# DE1_SIDE_SDRAM.net
KiCad netlist of a schematic drawn in Altium Designer
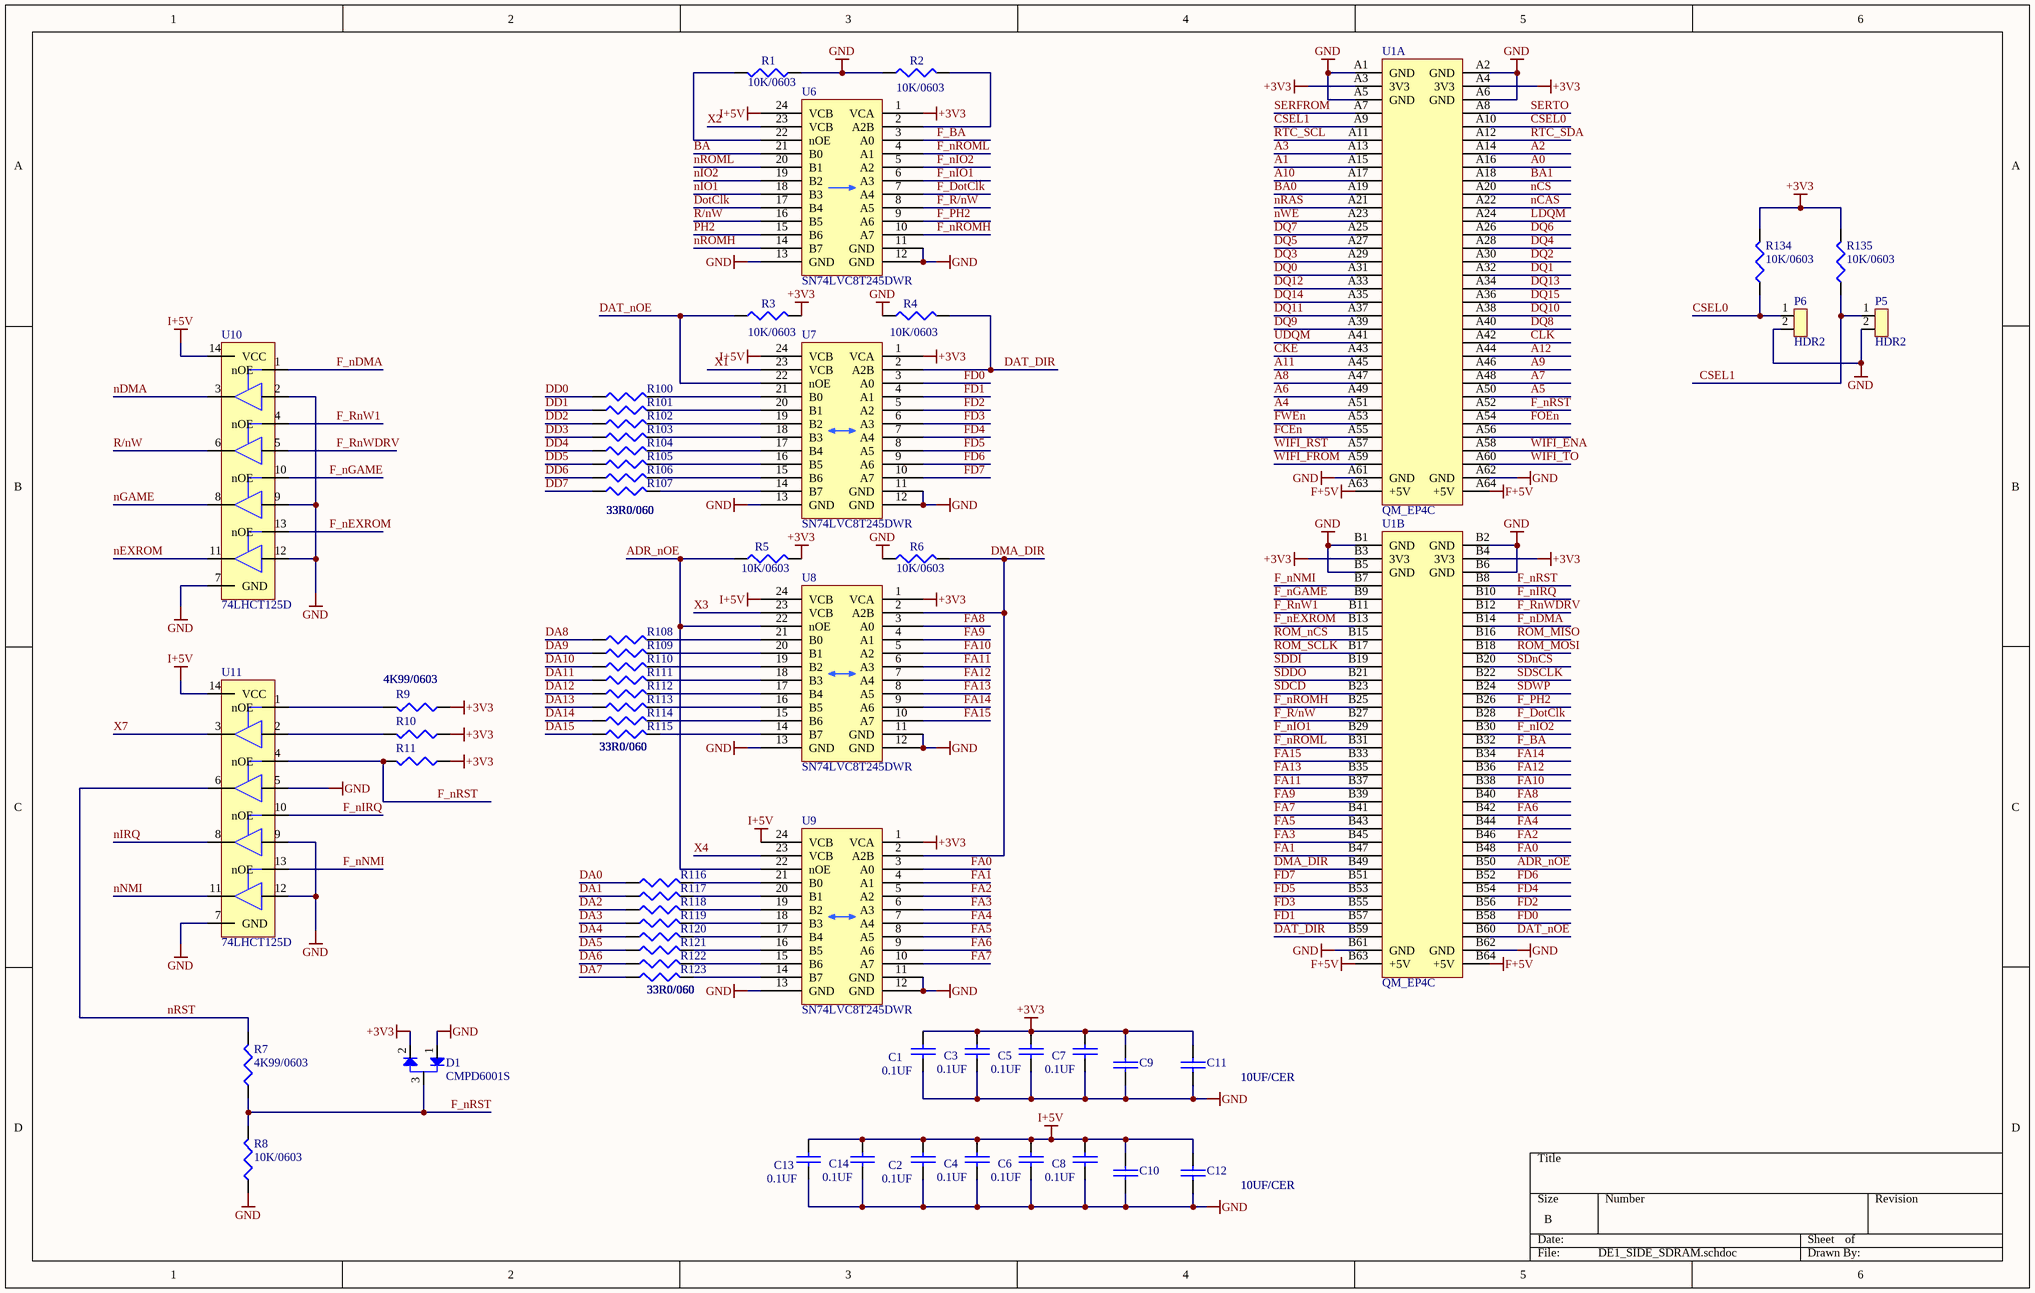
[diagram p0: DE1_SIDE_SDRAM.schdoc]

(export (version "E")
  (design (tool "Eeschema 10.0.6"))
  (components
    (comp (ref "C1")
      (value "0.1UF")
      (footprint "0603")
      (description "CAP .10UF 16V CERAMIC X7R 0603")
      (libsource (lib "*") (part "0.1UF"))
    )
    (comp (ref "C2")
      (value "0.1UF")
      (footprint "0603")
      (description "CAP .10UF 16V CERAMIC X7R 0603")
      (libsource (lib "*") (part "0.1UF"))
    )
    (comp (ref "C3")
      (value "0.1UF")
      (footprint "0603")
      (description "CAP .10UF 16V CERAMIC X7R 0603")
      (libsource (lib "*") (part "0.1UF"))
    )
    (comp (ref "C4")
      (value "0.1UF")
      (footprint "0603")
      (description "CAP .10UF 16V CERAMIC X7R 0603")
      (libsource (lib "*") (part "0.1UF"))
    )
    (comp (ref "C5")
      (value "0.1UF")
      (footprint "0603")
      (description "CAP .10UF 16V CERAMIC X7R 0603")
      (libsource (lib "*") (part "0.1UF"))
    )
    (comp (ref "C6")
      (value "0.1UF")
      (footprint "0603")
      (description "CAP .10UF 16V CERAMIC X7R 0603")
      (libsource (lib "*") (part "0.1UF"))
    )
    (comp (ref "C7")
      (value "0.1UF")
      (footprint "0603")
      (description "CAP .10UF 16V CERAMIC X7R 0603")
      (libsource (lib "*") (part "0.1UF"))
    )
    (comp (ref "C8")
      (value "0.1UF")
      (footprint "0603")
      (description "CAP .10UF 16V CERAMIC X7R 0603")
      (libsource (lib "*") (part "0.1UF"))
    )
    (comp (ref "C9")
      (value "10UF/CER")
      (footprint "0805")
      (description "10µF ±10% 25V Ceramic Capacitor X7S 0805")
      (libsource (lib "*") (part "10UF/CER"))
    )
    (comp (ref "C10")
      (value "10UF/CER")
      (footprint "0805")
      (description "10µF ±10% 25V Ceramic Capacitor X7S 0805")
      (libsource (lib "*") (part "10UF/CER"))
    )
    (comp (ref "C11")
      (value "10UF/CER")
      (footprint "0805")
      (description "10µF ±10% 25V Ceramic Capacitor X7S 0805")
      (libsource (lib "*") (part "10UF/CER"))
    )
    (comp (ref "C12")
      (value "10UF/CER")
      (footprint "0805")
      (description "10µF ±10% 25V Ceramic Capacitor X7S 0805")
      (libsource (lib "*") (part "10UF/CER"))
    )
    (comp (ref "C13")
      (value "0.1UF")
      (footprint "0603")
      (description "CAP .10UF 16V CERAMIC X7R 0603")
      (libsource (lib "*") (part "0.1UF"))
    )
    (comp (ref "C14")
      (value "0.1UF")
      (footprint "0603")
      (description "CAP .10UF 16V CERAMIC X7R 0603")
      (libsource (lib "*") (part "0.1UF"))
    )
    (comp (ref "D1")
      (value "CMPD6001S")
      (footprint "SOT-23")
      (description "Diode Array 1 Pair Series Connection Standard 75V 250mA Surface Mount TO-236-3, SC-59, SOT-23-3")
      (fields (field (name "MFG") "Central Semiconductor"))
      (libsource (lib "C64Interface") (part "CMPD6001S"))
    )
    (comp (ref "P5") (value "HDR2") (footprint "HDR2") (libsource (lib "C64Interface") (part "HDR2")))
    (comp (ref "P6") (value "HDR2") (footprint "HDR2") (libsource (lib "C64Interface") (part "HDR2")))
    (comp (ref "R1")
      (value "10K/0603")
      (footprint "0603")
      (description "RES 10.0K OHM 1/10W 1% 0603 SMD")
      (libsource (lib "*") (part "10K/0603"))
    )
    (comp (ref "R2")
      (value "10K/0603")
      (footprint "0603")
      (description "RES 10.0K OHM 1/10W 1% 0603 SMD")
      (libsource (lib "*") (part "10K/0603"))
    )
    (comp (ref "R3")
      (value "10K/0603")
      (footprint "0603")
      (description "RES 10.0K OHM 1/10W 1% 0603 SMD")
      (libsource (lib "*") (part "10K/0603"))
    )
    (comp (ref "R4")
      (value "10K/0603")
      (footprint "0603")
      (description "RES 10.0K OHM 1/10W 1% 0603 SMD")
      (libsource (lib "*") (part "10K/0603"))
    )
    (comp (ref "R5")
      (value "10K/0603")
      (footprint "0603")
      (description "RES 10.0K OHM 1/10W 1% 0603 SMD")
      (libsource (lib "*") (part "10K/0603"))
    )
    (comp (ref "R6")
      (value "10K/0603")
      (footprint "0603")
      (description "RES 10.0K OHM 1/10W 1% 0603 SMD")
      (libsource (lib "*") (part "10K/0603"))
    )
    (comp (ref "R7")
      (value "4K99/0603")
      (footprint "0603")
      (description "RES 4.99K OHM 1/10W 1% 0603 SMD")
      (fields (field (name "MFG") "Dale/Vishay"))
      (libsource (lib "C64Interface") (part "4K99/0603"))
    )
    (comp (ref "R8")
      (value "10K/0603")
      (footprint "0603")
      (description "RES 10.0K OHM 1/10W 1% 0603 SMD")
      (fields (field (name "MFG") "Dale/Vishay"))
      (libsource (lib "C64Interface") (part "10K/0603"))
    )
    (comp (ref "R9")
      (value "4K99/0603")
      (footprint "0603")
      (description "RES 4.99K OHM 1/10W 1% 0603 SMD")
      (fields (field (name "MFG") "Dale/Vishay"))
      (libsource (lib "C64Interface") (part "4K99/0603"))
    )
    (comp (ref "R10")
      (value "4K99/0603")
      (footprint "0603")
      (description "RES 4.99K OHM 1/10W 1% 0603 SMD")
      (fields (field (name "MFG") "Dale/Vishay"))
      (libsource (lib "C64Interface") (part "4K99/0603"))
    )
    (comp (ref "R11")
      (value "4K99/0603")
      (footprint "0603")
      (description "RES 4.99K OHM 1/10W 1% 0603 SMD")
      (fields (field (name "MFG") "Dale/Vishay"))
      (libsource (lib "C64Interface") (part "4K99/0603"))
    )
    (comp (ref "R100")
      (value "33R0/060")
      (footprint "0603")
      (description "33 Ohms ±1% 0.1W, 1/10W Chip Resistor 0603 (1608 Metric) Moisture Resistant Thick Film")
      (fields (field (name "MFG") "Yaego"))
      (libsource (lib "C64Interface") (part "33R0/060"))
    )
    (comp (ref "R101")
      (value "33R0/060")
      (footprint "0603")
      (description "33 Ohms ±1% 0.1W, 1/10W Chip Resistor 0603 (1608 Metric) Moisture Resistant Thick Film")
      (fields (field (name "MFG") "Yaego"))
      (libsource (lib "C64Interface") (part "33R0/060"))
    )
    (comp (ref "R102")
      (value "33R0/060")
      (footprint "0603")
      (description "33 Ohms ±1% 0.1W, 1/10W Chip Resistor 0603 (1608 Metric) Moisture Resistant Thick Film")
      (fields (field (name "MFG") "Yaego"))
      (libsource (lib "C64Interface") (part "33R0/060"))
    )
    (comp (ref "R103")
      (value "33R0/060")
      (footprint "0603")
      (description "33 Ohms ±1% 0.1W, 1/10W Chip Resistor 0603 (1608 Metric) Moisture Resistant Thick Film")
      (fields (field (name "MFG") "Yaego"))
      (libsource (lib "C64Interface") (part "33R0/060"))
    )
    (comp (ref "R104")
      (value "33R0/060")
      (footprint "0603")
      (description "33 Ohms ±1% 0.1W, 1/10W Chip Resistor 0603 (1608 Metric) Moisture Resistant Thick Film")
      (fields (field (name "MFG") "Yaego"))
      (libsource (lib "C64Interface") (part "33R0/060"))
    )
    (comp (ref "R105")
      (value "33R0/060")
      (footprint "0603")
      (description "33 Ohms ±1% 0.1W, 1/10W Chip Resistor 0603 (1608 Metric) Moisture Resistant Thick Film")
      (fields (field (name "MFG") "Yaego"))
      (libsource (lib "C64Interface") (part "33R0/060"))
    )
    (comp (ref "R106")
      (value "33R0/060")
      (footprint "0603")
      (description "33 Ohms ±1% 0.1W, 1/10W Chip Resistor 0603 (1608 Metric) Moisture Resistant Thick Film")
      (fields (field (name "MFG") "Yaego"))
      (libsource (lib "C64Interface") (part "33R0/060"))
    )
    (comp (ref "R107")
      (value "33R0/060")
      (footprint "0603")
      (description "33 Ohms ±1% 0.1W, 1/10W Chip Resistor 0603 (1608 Metric) Moisture Resistant Thick Film")
      (fields (field (name "MFG") "Yaego"))
      (libsource (lib "C64Interface") (part "33R0/060"))
    )
    (comp (ref "R108")
      (value "33R0/060")
      (footprint "0603")
      (description "33 Ohms ±1% 0.1W, 1/10W Chip Resistor 0603 (1608 Metric) Moisture Resistant Thick Film")
      (fields (field (name "MFG") "Yaego"))
      (libsource (lib "C64Interface") (part "33R0/060"))
    )
    (comp (ref "R109")
      (value "33R0/060")
      (footprint "0603")
      (description "33 Ohms ±1% 0.1W, 1/10W Chip Resistor 0603 (1608 Metric) Moisture Resistant Thick Film")
      (fields (field (name "MFG") "Yaego"))
      (libsource (lib "C64Interface") (part "33R0/060"))
    )
    (comp (ref "R110")
      (value "33R0/060")
      (footprint "0603")
      (description "33 Ohms ±1% 0.1W, 1/10W Chip Resistor 0603 (1608 Metric) Moisture Resistant Thick Film")
      (fields (field (name "MFG") "Yaego"))
      (libsource (lib "C64Interface") (part "33R0/060"))
    )
    (comp (ref "R111")
      (value "33R0/060")
      (footprint "0603")
      (description "33 Ohms ±1% 0.1W, 1/10W Chip Resistor 0603 (1608 Metric) Moisture Resistant Thick Film")
      (fields (field (name "MFG") "Yaego"))
      (libsource (lib "C64Interface") (part "33R0/060"))
    )
    (comp (ref "R112")
      (value "33R0/060")
      (footprint "0603")
      (description "33 Ohms ±1% 0.1W, 1/10W Chip Resistor 0603 (1608 Metric) Moisture Resistant Thick Film")
      (fields (field (name "MFG") "Yaego"))
      (libsource (lib "C64Interface") (part "33R0/060"))
    )
    (comp (ref "R113")
      (value "33R0/060")
      (footprint "0603")
      (description "33 Ohms ±1% 0.1W, 1/10W Chip Resistor 0603 (1608 Metric) Moisture Resistant Thick Film")
      (fields (field (name "MFG") "Yaego"))
      (libsource (lib "C64Interface") (part "33R0/060"))
    )
    (comp (ref "R114")
      (value "33R0/060")
      (footprint "0603")
      (description "33 Ohms ±1% 0.1W, 1/10W Chip Resistor 0603 (1608 Metric) Moisture Resistant Thick Film")
      (fields (field (name "MFG") "Yaego"))
      (libsource (lib "C64Interface") (part "33R0/060"))
    )
    (comp (ref "R115")
      (value "33R0/060")
      (footprint "0603")
      (description "33 Ohms ±1% 0.1W, 1/10W Chip Resistor 0603 (1608 Metric) Moisture Resistant Thick Film")
      (fields (field (name "MFG") "Yaego"))
      (libsource (lib "C64Interface") (part "33R0/060"))
    )
    (comp (ref "R116")
      (value "33R0/060")
      (footprint "0603")
      (description "33 Ohms ±1% 0.1W, 1/10W Chip Resistor 0603 (1608 Metric) Moisture Resistant Thick Film")
      (fields (field (name "MFG") "Yaego"))
      (libsource (lib "C64Interface") (part "33R0/060"))
    )
    (comp (ref "R117")
      (value "33R0/060")
      (footprint "0603")
      (description "33 Ohms ±1% 0.1W, 1/10W Chip Resistor 0603 (1608 Metric) Moisture Resistant Thick Film")
      (fields (field (name "MFG") "Yaego"))
      (libsource (lib "C64Interface") (part "33R0/060"))
    )
    (comp (ref "R118")
      (value "33R0/060")
      (footprint "0603")
      (description "33 Ohms ±1% 0.1W, 1/10W Chip Resistor 0603 (1608 Metric) Moisture Resistant Thick Film")
      (fields (field (name "MFG") "Yaego"))
      (libsource (lib "C64Interface") (part "33R0/060"))
    )
    (comp (ref "R119")
      (value "33R0/060")
      (footprint "0603")
      (description "33 Ohms ±1% 0.1W, 1/10W Chip Resistor 0603 (1608 Metric) Moisture Resistant Thick Film")
      (fields (field (name "MFG") "Yaego"))
      (libsource (lib "C64Interface") (part "33R0/060"))
    )
    (comp (ref "R120")
      (value "33R0/060")
      (footprint "0603")
      (description "33 Ohms ±1% 0.1W, 1/10W Chip Resistor 0603 (1608 Metric) Moisture Resistant Thick Film")
      (fields (field (name "MFG") "Yaego"))
      (libsource (lib "C64Interface") (part "33R0/060"))
    )
    (comp (ref "R121")
      (value "33R0/060")
      (footprint "0603")
      (description "33 Ohms ±1% 0.1W, 1/10W Chip Resistor 0603 (1608 Metric) Moisture Resistant Thick Film")
      (fields (field (name "MFG") "Yaego"))
      (libsource (lib "C64Interface") (part "33R0/060"))
    )
    (comp (ref "R122")
      (value "33R0/060")
      (footprint "0603")
      (description "33 Ohms ±1% 0.1W, 1/10W Chip Resistor 0603 (1608 Metric) Moisture Resistant Thick Film")
      (fields (field (name "MFG") "Yaego"))
      (libsource (lib "C64Interface") (part "33R0/060"))
    )
    (comp (ref "R123")
      (value "33R0/060")
      (footprint "0603")
      (description "33 Ohms ±1% 0.1W, 1/10W Chip Resistor 0603 (1608 Metric) Moisture Resistant Thick Film")
      (fields (field (name "MFG") "Yaego"))
      (libsource (lib "C64Interface") (part "33R0/060"))
    )
    (comp (ref "R134")
      (value "10K/0603")
      (footprint "0603")
      (description "RES 10.0K OHM 1/10W 1% 0603 SMD")
      (fields (field (name "MFG") "Dale/Vishay"))
      (libsource (lib "C64Interface") (part "10K/0603"))
    )
    (comp (ref "R135")
      (value "10K/0603")
      (footprint "0603")
      (description "RES 10.0K OHM 1/10W 1% 0603 SMD")
      (fields (field (name "MFG") "Dale/Vishay"))
      (libsource (lib "C64Interface") (part "10K/0603"))
    )
    (comp (ref "U1")
      (value "QM_EP4C")
      (footprint "QMTECH_EP4CE15")
      (libsource (lib "C64Interface") (part "QM_EP4C"))
    )
    (comp (ref "U6")
      (value "SN74LVC8T245DWR")
      (footprint "SOL-24")
      (description "Voltage Level Translator Bidirectional 1 Circuit 8 Channel 24-SOIC")
      (fields (field (name "MFG") "TI"))
      (libsource (lib "C64Interface") (part "SN74LVC8T245DWR"))
    )
    (comp (ref "U7")
      (value "SN74LVC8T245DWR")
      (footprint "SOL-24")
      (description "Voltage Level Translator Bidirectional 1 Circuit 8 Channel 24-SOIC")
      (fields (field (name "MFG") "TI"))
      (libsource (lib "C64Interface") (part "SN74LVC8T245DWR"))
    )
    (comp (ref "U8")
      (value "SN74LVC8T245DWR")
      (footprint "SOL-24")
      (description "Voltage Level Translator Bidirectional 1 Circuit 8 Channel 24-SOIC")
      (fields (field (name "MFG") "TI"))
      (libsource (lib "C64Interface") (part "SN74LVC8T245DWR"))
    )
    (comp (ref "U9")
      (value "SN74LVC8T245DWR")
      (footprint "SOL-24")
      (description "Voltage Level Translator Bidirectional 1 Circuit 8 Channel 24-SOIC")
      (fields (field (name "MFG") "TI"))
      (libsource (lib "C64Interface") (part "SN74LVC8T245DWR"))
    )
    (comp (ref "U10")
      (value "74LHCT125D")
      (footprint "SOP14")
      (description "Buffer, Non-Inverting 4 Element 1 Bit per Element 3-State Output 14-SOIC")
      (fields (field (name "MFG") "Nexpiria"))
      (libsource (lib "C64Interface") (part "74LHCT125D"))
    )
    (comp (ref "U11")
      (value "74LHCT125D")
      (footprint "SOP14")
      (description "Buffer, Non-Inverting 4 Element 1 Bit per Element 3-State Output 14-SOIC")
      (fields (field (name "MFG") "Nexpiria"))
      (libsource (lib "C64Interface") (part "74LHCT125D"))
    )
  )
  (nets
    (net (code "1") (name "+3V3") (class "Default")
      (node (ref "C1") (pin "1") (pintype "passive"))
      (node (ref "C11") (pin "2") (pintype "passive"))
      (node (ref "C3") (pin "1") (pintype "passive"))
      (node (ref "C5") (pin "1") (pintype "passive"))
      (node (ref "C7") (pin "1") (pintype "passive"))
      (node (ref "C9") (pin "2") (pintype "passive"))
      (node (ref "D1") (pin "2") (pintype "passive"))
      (node (ref "R10") (pin "1") (pintype "passive"))
      (node (ref "R11") (pin "1") (pintype "passive"))
      (node (ref "R134") (pin "2") (pintype "passive"))
      (node (ref "R135") (pin "2") (pintype "passive"))
      (node (ref "R3") (pin "2") (pintype "passive"))
      (node (ref "R5") (pin "2") (pintype "passive"))
      (node (ref "R9") (pin "1") (pintype "passive"))
      (node (ref "U1") (pin "A3") (pinfunction "3V3_A3") (pintype "passive"))
      (node (ref "U1") (pin "A4") (pinfunction "3V3_A4") (pintype "passive"))
      (node (ref "U1") (pin "B3") (pinfunction "3V3_B3") (pintype "passive"))
      (node (ref "U1") (pin "B4") (pinfunction "3V3_B4") (pintype "passive"))
      (node (ref "U6") (pin "1") (pinfunction "VCA_1") (pintype "passive"))
      (node (ref "U7") (pin "1") (pinfunction "VCA_1") (pintype "passive"))
      (node (ref "U8") (pin "1") (pinfunction "VCA_1") (pintype "passive"))
      (node (ref "U9") (pin "1") (pinfunction "VCA_1") (pintype "passive"))
    )
    (net (code "2") (name "/A0") (class "Default") (node (ref "U1") (pin "A16") (pintype "passive")))
    (net (code "3") (name "/A1") (class "Default") (node (ref "U1") (pin "A15") (pintype "passive")))
    (net (code "4") (name "/A2") (class "Default") (node (ref "U1") (pin "A14") (pintype "passive")))
    (net (code "5") (name "/A3") (class "Default") (node (ref "U1") (pin "A13") (pintype "passive")))
    (net (code "6") (name "/A4") (class "Default") (node (ref "U1") (pin "A51") (pintype "passive")))
    (net (code "7") (name "/A5") (class "Default") (node (ref "U1") (pin "A50") (pintype "passive")))
    (net (code "8") (name "/A6") (class "Default") (node (ref "U1") (pin "A49") (pintype "passive")))
    (net (code "9") (name "/A7") (class "Default") (node (ref "U1") (pin "A48") (pintype "passive")))
    (net (code "10") (name "/A8") (class "Default") (node (ref "U1") (pin "A47") (pintype "passive")))
    (net (code "11") (name "/A9") (class "Default") (node (ref "U1") (pin "A46") (pintype "passive")))
    (net (code "12") (name "/A10") (class "Default") (node (ref "U1") (pin "A17") (pintype "passive")))
    (net (code "13") (name "/A11") (class "Default") (node (ref "U1") (pin "A45") (pintype "passive")))
    (net (code "14") (name "/A12") (class "Default") (node (ref "U1") (pin "A44") (pintype "passive")))
    (net (code "15") (name "/ADR_nOE") (class "Default")
      (node (ref "R5") (pin "1") (pintype "passive"))
      (node (ref "U1") (pin "B50") (pintype "passive"))
      (node (ref "U8") (pin "22") (pinfunction "nOE_22") (pintype "passive"))
      (node (ref "U9") (pin "22") (pinfunction "nOE_22") (pintype "passive"))
    )
    (net (code "16") (name "/BA") (class "Default")
      (node (ref "U6") (pin "21") (pinfunction "B0_21") (pintype "passive"))
    )
    (net (code "17") (name "/BA0") (class "Default") (node (ref "U1") (pin "A19") (pintype "passive")))
    (net (code "18") (name "/BA1") (class "Default") (node (ref "U1") (pin "A18") (pintype "passive")))
    (net (code "19") (name "/CKE") (class "Default") (node (ref "U1") (pin "A43") (pintype "passive")))
    (net (code "20") (name "/CLK") (class "Default") (node (ref "U1") (pin "A42") (pintype "passive")))
    (net (code "21") (name "/CSEL0") (class "Default")
      (node (ref "P6") (pin "1") (pintype "passive"))
      (node (ref "R134") (pin "1") (pintype "passive"))
      (node (ref "U1") (pin "A10") (pintype "passive"))
    )
    (net (code "22") (name "/CSEL1") (class "Default")
      (node (ref "P5") (pin "1") (pintype "passive"))
      (node (ref "R135") (pin "1") (pintype "passive"))
      (node (ref "U1") (pin "A9") (pintype "passive"))
    )
    (net (code "23") (name "/DA0") (class "Default") (node (ref "R116") (pin "1") (pintype "passive")))
    (net (code "24") (name "/DA1") (class "Default") (node (ref "R117") (pin "1") (pintype "passive")))
    (net (code "25") (name "/DA2") (class "Default") (node (ref "R118") (pin "1") (pintype "passive")))
    (net (code "26") (name "/DA3") (class "Default") (node (ref "R119") (pin "1") (pintype "passive")))
    (net (code "27") (name "/DA4") (class "Default") (node (ref "R120") (pin "1") (pintype "passive")))
    (net (code "28") (name "/DA5") (class "Default") (node (ref "R121") (pin "1") (pintype "passive")))
    (net (code "29") (name "/DA6") (class "Default") (node (ref "R122") (pin "1") (pintype "passive")))
    (net (code "30") (name "/DA7") (class "Default") (node (ref "R123") (pin "1") (pintype "passive")))
    (net (code "31") (name "/DA8") (class "Default") (node (ref "R108") (pin "1") (pintype "passive")))
    (net (code "32") (name "/DA9") (class "Default") (node (ref "R109") (pin "1") (pintype "passive")))
    (net (code "33") (name "/DA10") (class "Default") (node (ref "R110") (pin "1") (pintype "passive")))
    (net (code "34") (name "/DA11") (class "Default") (node (ref "R111") (pin "1") (pintype "passive")))
    (net (code "35") (name "/DA12") (class "Default") (node (ref "R112") (pin "1") (pintype "passive")))
    (net (code "36") (name "/DA13") (class "Default") (node (ref "R113") (pin "1") (pintype "passive")))
    (net (code "37") (name "/DA14") (class "Default") (node (ref "R114") (pin "1") (pintype "passive")))
    (net (code "38") (name "/DA15") (class "Default") (node (ref "R115") (pin "1") (pintype "passive")))
    (net (code "39") (name "/DAT_DIR") (class "Default")
      (node (ref "R4") (pin "2") (pintype "passive"))
      (node (ref "U1") (pin "B59") (pintype "passive"))
      (node (ref "U7") (pin "2") (pinfunction "A2B_2") (pintype "passive"))
    )
    (net (code "40") (name "/DAT_nOE") (class "Default")
      (node (ref "R3") (pin "1") (pintype "passive"))
      (node (ref "U1") (pin "B60") (pintype "passive"))
      (node (ref "U7") (pin "22") (pinfunction "nOE_22") (pintype "passive"))
    )
    (net (code "41") (name "/DD0") (class "Default") (node (ref "R100") (pin "1") (pintype "passive")))
    (net (code "42") (name "/DD1") (class "Default") (node (ref "R101") (pin "1") (pintype "passive")))
    (net (code "43") (name "/DD2") (class "Default") (node (ref "R102") (pin "1") (pintype "passive")))
    (net (code "44") (name "/DD3") (class "Default") (node (ref "R103") (pin "1") (pintype "passive")))
    (net (code "45") (name "/DD4") (class "Default") (node (ref "R104") (pin "1") (pintype "passive")))
    (net (code "46") (name "/DD5") (class "Default") (node (ref "R105") (pin "1") (pintype "passive")))
    (net (code "47") (name "/DD6") (class "Default") (node (ref "R106") (pin "1") (pintype "passive")))
    (net (code "48") (name "/DD7") (class "Default") (node (ref "R107") (pin "1") (pintype "passive")))
    (net (code "49") (name "/DMA_DIR") (class "Default")
      (node (ref "R6") (pin "2") (pintype "passive"))
      (node (ref "U1") (pin "B49") (pintype "passive"))
      (node (ref "U8") (pin "2") (pinfunction "A2B_2") (pintype "passive"))
      (node (ref "U9") (pin "2") (pinfunction "A2B_2") (pintype "passive"))
    )
    (net (code "50") (name "/DQ0") (class "Default") (node (ref "U1") (pin "A31") (pintype "passive")))
    (net (code "51") (name "/DQ1") (class "Default") (node (ref "U1") (pin "A32") (pintype "passive")))
    (net (code "52") (name "/DQ2") (class "Default") (node (ref "U1") (pin "A30") (pintype "passive")))
    (net (code "53") (name "/DQ3") (class "Default") (node (ref "U1") (pin "A29") (pintype "passive")))
    (net (code "54") (name "/DQ4") (class "Default") (node (ref "U1") (pin "A28") (pintype "passive")))
    (net (code "55") (name "/DQ5") (class "Default") (node (ref "U1") (pin "A27") (pintype "passive")))
    (net (code "56") (name "/DQ6") (class "Default") (node (ref "U1") (pin "A26") (pintype "passive")))
    (net (code "57") (name "/DQ7") (class "Default") (node (ref "U1") (pin "A25") (pintype "passive")))
    (net (code "58") (name "/DQ8") (class "Default") (node (ref "U1") (pin "A40") (pintype "passive")))
    (net (code "59") (name "/DQ9") (class "Default") (node (ref "U1") (pin "A39") (pintype "passive")))
    (net (code "60") (name "/DQ10") (class "Default") (node (ref "U1") (pin "A38") (pintype "passive")))
    (net (code "61") (name "/DQ11") (class "Default") (node (ref "U1") (pin "A37") (pintype "passive")))
    (net (code "62") (name "/DQ12") (class "Default") (node (ref "U1") (pin "A33") (pintype "passive")))
    (net (code "63") (name "/DQ13") (class "Default") (node (ref "U1") (pin "A34") (pintype "passive")))
    (net (code "64") (name "/DQ14") (class "Default") (node (ref "U1") (pin "A35") (pintype "passive")))
    (net (code "65") (name "/DQ15") (class "Default") (node (ref "U1") (pin "A36") (pintype "passive")))
    (net (code "66") (name "/DotClk") (class "Default")
      (node (ref "U6") (pin "17") (pinfunction "B4_17") (pintype "passive"))
    )
    (net (code "67") (name "/FA0") (class "Default")
      (node (ref "U1") (pin "B48") (pintype "passive"))
      (node (ref "U9") (pin "3") (pinfunction "A0_3") (pintype "passive"))
    )
    (net (code "68") (name "/FA1") (class "Default")
      (node (ref "U1") (pin "B47") (pintype "passive"))
      (node (ref "U9") (pin "4") (pinfunction "A1_4") (pintype "passive"))
    )
    (net (code "69") (name "/FA2") (class "Default")
      (node (ref "U1") (pin "B46") (pintype "passive"))
      (node (ref "U9") (pin "5") (pinfunction "A2_5") (pintype "passive"))
    )
    (net (code "70") (name "/FA3") (class "Default")
      (node (ref "U1") (pin "B45") (pintype "passive"))
      (node (ref "U9") (pin "6") (pinfunction "A3_6") (pintype "passive"))
    )
    (net (code "71") (name "/FA4") (class "Default")
      (node (ref "U1") (pin "B44") (pintype "passive"))
      (node (ref "U9") (pin "7") (pinfunction "A4_7") (pintype "passive"))
    )
    (net (code "72") (name "/FA5") (class "Default")
      (node (ref "U1") (pin "B43") (pintype "passive"))
      (node (ref "U9") (pin "8") (pinfunction "A5_8") (pintype "passive"))
    )
    (net (code "73") (name "/FA6") (class "Default")
      (node (ref "U1") (pin "B42") (pintype "passive"))
      (node (ref "U9") (pin "9") (pinfunction "A6_9") (pintype "passive"))
    )
    (net (code "74") (name "/FA7") (class "Default")
      (node (ref "U1") (pin "B41") (pintype "passive"))
      (node (ref "U9") (pin "10") (pinfunction "A7_10") (pintype "passive"))
    )
    (net (code "75") (name "/FA8") (class "Default")
      (node (ref "U1") (pin "B40") (pintype "passive"))
      (node (ref "U8") (pin "3") (pinfunction "A0_3") (pintype "passive"))
    )
    (net (code "76") (name "/FA9") (class "Default")
      (node (ref "U1") (pin "B39") (pintype "passive"))
      (node (ref "U8") (pin "4") (pinfunction "A1_4") (pintype "passive"))
    )
    (net (code "77") (name "/FA10") (class "Default")
      (node (ref "U1") (pin "B38") (pintype "passive"))
      (node (ref "U8") (pin "5") (pinfunction "A2_5") (pintype "passive"))
    )
    (net (code "78") (name "/FA11") (class "Default")
      (node (ref "U1") (pin "B37") (pintype "passive"))
      (node (ref "U8") (pin "6") (pinfunction "A3_6") (pintype "passive"))
    )
    (net (code "79") (name "/FA12") (class "Default")
      (node (ref "U1") (pin "B36") (pintype "passive"))
      (node (ref "U8") (pin "7") (pinfunction "A4_7") (pintype "passive"))
    )
    (net (code "80") (name "/FA13") (class "Default")
      (node (ref "U1") (pin "B35") (pintype "passive"))
      (node (ref "U8") (pin "8") (pinfunction "A5_8") (pintype "passive"))
    )
    (net (code "81") (name "/FA14") (class "Default")
      (node (ref "U1") (pin "B34") (pintype "passive"))
      (node (ref "U8") (pin "9") (pinfunction "A6_9") (pintype "passive"))
    )
    (net (code "82") (name "/FA15") (class "Default")
      (node (ref "U1") (pin "B33") (pintype "passive"))
      (node (ref "U8") (pin "10") (pinfunction "A7_10") (pintype "passive"))
    )
    (net (code "83") (name "/FCEn") (class "Default") (node (ref "U1") (pin "A55") (pintype "passive")))
    (net (code "84") (name "/FD0") (class "Default")
      (node (ref "U1") (pin "B58") (pintype "passive"))
      (node (ref "U7") (pin "3") (pinfunction "A0_3") (pintype "passive"))
    )
    (net (code "85") (name "/FD1") (class "Default")
      (node (ref "U1") (pin "B57") (pintype "passive"))
      (node (ref "U7") (pin "4") (pinfunction "A1_4") (pintype "passive"))
    )
    (net (code "86") (name "/FD2") (class "Default")
      (node (ref "U1") (pin "B56") (pintype "passive"))
      (node (ref "U7") (pin "5") (pinfunction "A2_5") (pintype "passive"))
    )
    (net (code "87") (name "/FD3") (class "Default")
      (node (ref "U1") (pin "B55") (pintype "passive"))
      (node (ref "U7") (pin "6") (pinfunction "A3_6") (pintype "passive"))
    )
    (net (code "88") (name "/FD4") (class "Default")
      (node (ref "U1") (pin "B54") (pintype "passive"))
      (node (ref "U7") (pin "7") (pinfunction "A4_7") (pintype "passive"))
    )
    (net (code "89") (name "/FD5") (class "Default")
      (node (ref "U1") (pin "B53") (pintype "passive"))
      (node (ref "U7") (pin "8") (pinfunction "A5_8") (pintype "passive"))
    )
    (net (code "90") (name "/FD6") (class "Default")
      (node (ref "U1") (pin "B52") (pintype "passive"))
      (node (ref "U7") (pin "9") (pinfunction "A6_9") (pintype "passive"))
    )
    (net (code "91") (name "/FD7") (class "Default")
      (node (ref "U1") (pin "B51") (pintype "passive"))
      (node (ref "U7") (pin "10") (pinfunction "A7_10") (pintype "passive"))
    )
    (net (code "92") (name "/FOEn") (class "Default") (node (ref "U1") (pin "A54") (pintype "passive")))
    (net (code "93") (name "/FWEn") (class "Default") (node (ref "U1") (pin "A53") (pintype "passive")))
    (net (code "94") (name "/F_BA") (class "Default")
      (node (ref "U1") (pin "B32") (pintype "passive"))
      (node (ref "U6") (pin "3") (pinfunction "A0_3") (pintype "passive"))
    )
    (net (code "95") (name "/F_DotClk") (class "Default")
      (node (ref "U1") (pin "B28") (pintype "passive"))
      (node (ref "U6") (pin "7") (pinfunction "A4_7") (pintype "passive"))
    )
    (net (code "96") (name "/F_PH2") (class "Default")
      (node (ref "U1") (pin "B26") (pintype "passive"))
      (node (ref "U6") (pin "9") (pinfunction "A6_9") (pintype "passive"))
    )
    (net (code "97") (name "/F_RnW1") (class "Default")
      (node (ref "U1") (pin "B11") (pintype "passive"))
      (node (ref "U10") (pin "4") (pinfunction "nOE_4") (pintype "passive"))
    )
    (net (code "98") (name "/F_RnWDRV") (class "Default")
      (node (ref "U1") (pin "B12") (pintype "passive"))
      (node (ref "U10") (pin "5") (pintype "passive"))
    )
    (net (code "99") (name "/F_R{slash}nW") (class "Default")
      (node (ref "U1") (pin "B27") (pintype "passive"))
      (node (ref "U6") (pin "8") (pinfunction "A5_8") (pintype "passive"))
    )
    (net (code "100") (name "/F_nDMA") (class "Default")
      (node (ref "U1") (pin "B14") (pintype "passive"))
      (node (ref "U10") (pin "1") (pinfunction "nOE_1") (pintype "passive"))
    )
    (net (code "101") (name "/F_nEXROM") (class "Default")
      (node (ref "U1") (pin "B13") (pintype "passive"))
      (node (ref "U10") (pin "13") (pinfunction "nOE_13") (pintype "passive"))
    )
    (net (code "102") (name "/F_nGAME") (class "Default")
      (node (ref "U1") (pin "B9") (pintype "passive"))
      (node (ref "U10") (pin "10") (pinfunction "nOE_10") (pintype "passive"))
    )
    (net (code "103") (name "/F_nIO1") (class "Default")
      (node (ref "U1") (pin "B29") (pintype "passive"))
      (node (ref "U6") (pin "6") (pinfunction "A3_6") (pintype "passive"))
    )
    (net (code "104") (name "/F_nIO2") (class "Default")
      (node (ref "U1") (pin "B30") (pintype "passive"))
      (node (ref "U6") (pin "5") (pinfunction "A2_5") (pintype "passive"))
    )
    (net (code "105") (name "/F_nIRQ") (class "Default")
      (node (ref "U1") (pin "B10") (pintype "passive"))
      (node (ref "U11") (pin "10") (pinfunction "nOE_10") (pintype "passive"))
    )
    (net (code "106") (name "/F_nNMI") (class "Default")
      (node (ref "U1") (pin "B7") (pintype "passive"))
      (node (ref "U11") (pin "13") (pinfunction "nOE_13") (pintype "passive"))
    )
    (net (code "107") (name "/F_nROMH") (class "Default")
      (node (ref "U1") (pin "B25") (pintype "passive"))
      (node (ref "U6") (pin "10") (pinfunction "A7_10") (pintype "passive"))
    )
    (net (code "108") (name "/F_nROML") (class "Default")
      (node (ref "U1") (pin "B31") (pintype "passive"))
      (node (ref "U6") (pin "4") (pinfunction "A1_4") (pintype "passive"))
    )
    (net (code "109") (name "/F_nRST") (class "Default")
      (node (ref "D1") (pin "3") (pintype "passive"))
      (node (ref "R11") (pin "2") (pintype "passive"))
      (node (ref "R7") (pin "1") (pintype "passive"))
      (node (ref "R8") (pin "2") (pintype "passive"))
      (node (ref "U1") (pin "A52") (pintype "passive"))
      (node (ref "U1") (pin "B8") (pintype "passive"))
      (node (ref "U11") (pin "4") (pinfunction "nOE_4") (pintype "passive"))
    )
    (net (code "110") (name "/LDQM") (class "Default") (node (ref "U1") (pin "A24") (pintype "passive")))
    (net (code "111") (name "/PH2") (class "Default")
      (node (ref "U6") (pin "15") (pinfunction "B6_15") (pintype "passive"))
    )
    (net (code "112") (name "/ROM_MISO") (class "Default") (node (ref "U1") (pin "B16") (pintype "passive")))
    (net (code "113") (name "/ROM_MOSI") (class "Default") (node (ref "U1") (pin "B18") (pintype "passive")))
    (net (code "114") (name "/ROM_SCLK") (class "Default") (node (ref "U1") (pin "B17") (pintype "passive")))
    (net (code "115") (name "/ROM_nCS") (class "Default") (node (ref "U1") (pin "B15") (pintype "passive")))
    (net (code "116") (name "/RTC_SCL") (class "Default") (node (ref "U1") (pin "A11") (pintype "passive")))
    (net (code "117") (name "/RTC_SDA") (class "Default") (node (ref "U1") (pin "A12") (pintype "passive")))
    (net (code "118") (name "/R{slash}nW") (class "Default")
      (node (ref "U10") (pin "6") (pintype "passive"))
      (node (ref "U6") (pin "16") (pinfunction "B5_16") (pintype "passive"))
    )
    (net (code "119") (name "/SDCD") (class "Default") (node (ref "U1") (pin "B23") (pintype "passive")))
    (net (code "120") (name "/SDDI") (class "Default") (node (ref "U1") (pin "B19") (pintype "passive")))
    (net (code "121") (name "/SDDO") (class "Default") (node (ref "U1") (pin "B21") (pintype "passive")))
    (net (code "122") (name "/SDSCLK") (class "Default") (node (ref "U1") (pin "B22") (pintype "passive")))
    (net (code "123") (name "/SDWP") (class "Default") (node (ref "U1") (pin "B24") (pintype "passive")))
    (net (code "124") (name "/SDnCS") (class "Default") (node (ref "U1") (pin "B20") (pintype "passive")))
    (net (code "125") (name "/SERFROM") (class "Default") (node (ref "U1") (pin "A7") (pintype "passive")))
    (net (code "126") (name "/SERTO") (class "Default") (node (ref "U1") (pin "A8") (pintype "passive")))
    (net (code "127") (name "/UDQM") (class "Default") (node (ref "U1") (pin "A41") (pintype "passive")))
    (net (code "128") (name "/WIFI_ENA") (class "Default") (node (ref "U1") (pin "A58") (pintype "passive")))
    (net (code "129") (name "/WIFI_FROM") (class "Default") (node (ref "U1") (pin "A59") (pintype "passive")))
    (net (code "130") (name "/WIFI_RST") (class "Default") (node (ref "U1") (pin "A57") (pintype "passive")))
    (net (code "131") (name "/WIFI_TO") (class "Default") (node (ref "U1") (pin "A60") (pintype "passive")))
    (net (code "132") (name "/X1") (class "Default")
      (node (ref "U7") (pin "23") (pinfunction "VCB_23") (pintype "passive"))
    )
    (net (code "133") (name "/X2") (class "Default")
      (node (ref "U6") (pin "23") (pinfunction "VCB_23") (pintype "passive"))
    )
    (net (code "134") (name "/X3") (class "Default")
      (node (ref "U8") (pin "23") (pinfunction "VCB_23") (pintype "passive"))
    )
    (net (code "135") (name "/X4") (class "Default")
      (node (ref "U9") (pin "23") (pinfunction "VCB_23") (pintype "passive"))
    )
    (net (code "136") (name "/X7") (class "Default") (node (ref "U11") (pin "3") (pintype "passive")))
    (net (code "137") (name "/nCAS") (class "Default") (node (ref "U1") (pin "A22") (pintype "passive")))
    (net (code "138") (name "/nCS") (class "Default") (node (ref "U1") (pin "A20") (pintype "passive")))
    (net (code "139") (name "/nDMA") (class "Default") (node (ref "U10") (pin "3") (pintype "passive")))
    (net (code "140") (name "/nEXROM") (class "Default") (node (ref "U10") (pin "11") (pintype "passive")))
    (net (code "141") (name "/nGAME") (class "Default") (node (ref "U10") (pin "8") (pintype "passive")))
    (net (code "142") (name "/nIO1") (class "Default")
      (node (ref "U6") (pin "18") (pinfunction "B3_18") (pintype "passive"))
    )
    (net (code "143") (name "/nIO2") (class "Default")
      (node (ref "U6") (pin "19") (pinfunction "B2_19") (pintype "passive"))
    )
    (net (code "144") (name "/nIRQ") (class "Default") (node (ref "U11") (pin "8") (pintype "passive")))
    (net (code "145") (name "/nNMI") (class "Default") (node (ref "U11") (pin "11") (pintype "passive")))
    (net (code "146") (name "/nRAS") (class "Default") (node (ref "U1") (pin "A21") (pintype "passive")))
    (net (code "147") (name "/nROMH") (class "Default")
      (node (ref "U6") (pin "14") (pinfunction "B7_14") (pintype "passive"))
    )
    (net (code "148") (name "/nROML") (class "Default")
      (node (ref "U6") (pin "20") (pinfunction "B1_20") (pintype "passive"))
    )
    (net (code "149") (name "/nRST") (class "Default")
      (node (ref "R7") (pin "2") (pintype "passive"))
      (node (ref "U11") (pin "6") (pintype "passive"))
    )
    (net (code "150") (name "/nWE") (class "Default") (node (ref "U1") (pin "A23") (pintype "passive")))
    (net (code "151") (name "F+5V") (class "Default")
      (node (ref "U1") (pin "A63") (pinfunction "+5V_A63") (pintype "passive"))
      (node (ref "U1") (pin "A64") (pinfunction "+5V_A64") (pintype "passive"))
      (node (ref "U1") (pin "B63") (pinfunction "+5V_B63") (pintype "passive"))
      (node (ref "U1") (pin "B64") (pinfunction "+5V_B64") (pintype "passive"))
    )
    (net (code "152") (name "GND") (class "Default")
      (node (ref "C1") (pin "2") (pintype "passive"))
      (node (ref "C10") (pin "1") (pintype "passive"))
      (node (ref "C11") (pin "1") (pintype "passive"))
      (node (ref "C12") (pin "1") (pintype "passive"))
      (node (ref "C13") (pin "2") (pintype "passive"))
      (node (ref "C14") (pin "2") (pintype "passive"))
      (node (ref "C2") (pin "2") (pintype "passive"))
      (node (ref "C3") (pin "2") (pintype "passive"))
      (node (ref "C4") (pin "2") (pintype "passive"))
      (node (ref "C5") (pin "2") (pintype "passive"))
      (node (ref "C6") (pin "2") (pintype "passive"))
      (node (ref "C7") (pin "2") (pintype "passive"))
      (node (ref "C8") (pin "2") (pintype "passive"))
      (node (ref "C9") (pin "1") (pintype "passive"))
      (node (ref "D1") (pin "1") (pintype "passive"))
      (node (ref "P5") (pin "2") (pintype "passive"))
      (node (ref "P6") (pin "2") (pintype "passive"))
      (node (ref "R1") (pin "1") (pintype "passive"))
      (node (ref "R2") (pin "1") (pintype "passive"))
      (node (ref "R4") (pin "1") (pintype "passive"))
      (node (ref "R6") (pin "1") (pintype "passive"))
      (node (ref "R8") (pin "1") (pintype "passive"))
      (node (ref "U1") (pin "A1") (pinfunction "GND_A1") (pintype "passive"))
      (node (ref "U1") (pin "A2") (pinfunction "GND_A2") (pintype "passive"))
      (node (ref "U1") (pin "A5") (pinfunction "GND_A5") (pintype "passive"))
      (node (ref "U1") (pin "A6") (pinfunction "GND_A6") (pintype "passive"))
      (node (ref "U1") (pin "A61") (pinfunction "GND_A61") (pintype "passive"))
      (node (ref "U1") (pin "A62") (pinfunction "GND_A62") (pintype "passive"))
      (node (ref "U1") (pin "B1") (pinfunction "GND_B1") (pintype "passive"))
      (node (ref "U1") (pin "B2") (pinfunction "GND_B2") (pintype "passive"))
      (node (ref "U1") (pin "B5") (pinfunction "GND_B5") (pintype "passive"))
      (node (ref "U1") (pin "B6") (pinfunction "GND_B6") (pintype "passive"))
      (node (ref "U1") (pin "B61") (pinfunction "GND_B61") (pintype "passive"))
      (node (ref "U1") (pin "B62") (pinfunction "GND_B62") (pintype "passive"))
      (node (ref "U10") (pin "12") (pintype "passive"))
      (node (ref "U10") (pin "2") (pintype "passive"))
      (node (ref "U10") (pin "7") (pinfunction "GND_7") (pintype "passive"))
      (node (ref "U10") (pin "9") (pintype "passive"))
      (node (ref "U11") (pin "12") (pintype "passive"))
      (node (ref "U11") (pin "5") (pintype "passive"))
      (node (ref "U11") (pin "7") (pinfunction "GND_7") (pintype "passive"))
      (node (ref "U11") (pin "9") (pintype "passive"))
      (node (ref "U6") (pin "11") (pinfunction "GND_11") (pintype "passive"))
      (node (ref "U6") (pin "12") (pinfunction "GND_12") (pintype "passive"))
      (node (ref "U6") (pin "13") (pinfunction "GND_13") (pintype "passive"))
      (node (ref "U7") (pin "11") (pinfunction "GND_11") (pintype "passive"))
      (node (ref "U7") (pin "12") (pinfunction "GND_12") (pintype "passive"))
      (node (ref "U7") (pin "13") (pinfunction "GND_13") (pintype "passive"))
      (node (ref "U8") (pin "11") (pinfunction "GND_11") (pintype "passive"))
      (node (ref "U8") (pin "12") (pinfunction "GND_12") (pintype "passive"))
      (node (ref "U8") (pin "13") (pinfunction "GND_13") (pintype "passive"))
      (node (ref "U9") (pin "11") (pinfunction "GND_11") (pintype "passive"))
      (node (ref "U9") (pin "12") (pinfunction "GND_12") (pintype "passive"))
      (node (ref "U9") (pin "13") (pinfunction "GND_13") (pintype "passive"))
    )
    (net (code "153") (name "I+5V") (class "Default")
      (node (ref "C10") (pin "2") (pintype "passive"))
      (node (ref "C12") (pin "2") (pintype "passive"))
      (node (ref "C13") (pin "1") (pintype "passive"))
      (node (ref "C14") (pin "1") (pintype "passive"))
      (node (ref "C2") (pin "1") (pintype "passive"))
      (node (ref "C4") (pin "1") (pintype "passive"))
      (node (ref "C6") (pin "1") (pintype "passive"))
      (node (ref "C8") (pin "1") (pintype "passive"))
      (node (ref "U10") (pin "14") (pinfunction "VCC_14") (pintype "passive"))
      (node (ref "U11") (pin "14") (pinfunction "VCC_14") (pintype "passive"))
      (node (ref "U6") (pin "24") (pinfunction "VCB_24") (pintype "passive"))
      (node (ref "U7") (pin "24") (pinfunction "VCB_24") (pintype "passive"))
      (node (ref "U8") (pin "24") (pinfunction "VCB_24") (pintype "passive"))
      (node (ref "U9") (pin "24") (pinfunction "VCB_24") (pintype "passive"))
    )
    (net (code "154") (name "Net-(R9-Pad2)") (class "Default")
      (node (ref "R9") (pin "2") (pintype "passive"))
      (node (ref "U11") (pin "1") (pinfunction "nOE_1") (pintype "passive"))
    )
    (net (code "155") (name "Net-(R10-Pad2)") (class "Default")
      (node (ref "R10") (pin "2") (pintype "passive"))
      (node (ref "U11") (pin "2") (pintype "passive"))
    )
    (net (code "156") (name "Net-(U6-A2B)") (class "Default")
      (node (ref "R2") (pin "2") (pintype "passive"))
      (node (ref "U6") (pin "2") (pinfunction "A2B_2") (pintype "passive"))
    )
    (net (code "157") (name "Net-(U6-nOE)") (class "Default")
      (node (ref "R1") (pin "2") (pintype "passive"))
      (node (ref "U6") (pin "22") (pinfunction "nOE_22") (pintype "passive"))
    )
    (net (code "158") (name "Net-(U7-B0)") (class "Default")
      (node (ref "R100") (pin "2") (pintype "passive"))
      (node (ref "U7") (pin "21") (pinfunction "B0_21") (pintype "passive"))
    )
    (net (code "159") (name "Net-(U7-B1)") (class "Default")
      (node (ref "R101") (pin "2") (pintype "passive"))
      (node (ref "U7") (pin "20") (pinfunction "B1_20") (pintype "passive"))
    )
    (net (code "160") (name "Net-(U7-B2)") (class "Default")
      (node (ref "R102") (pin "2") (pintype "passive"))
      (node (ref "U7") (pin "19") (pinfunction "B2_19") (pintype "passive"))
    )
    (net (code "161") (name "Net-(U7-B3)") (class "Default")
      (node (ref "R103") (pin "2") (pintype "passive"))
      (node (ref "U7") (pin "18") (pinfunction "B3_18") (pintype "passive"))
    )
    (net (code "162") (name "Net-(U7-B4)") (class "Default")
      (node (ref "R104") (pin "2") (pintype "passive"))
      (node (ref "U7") (pin "17") (pinfunction "B4_17") (pintype "passive"))
    )
    (net (code "163") (name "Net-(U7-B5)") (class "Default")
      (node (ref "R105") (pin "2") (pintype "passive"))
      (node (ref "U7") (pin "16") (pinfunction "B5_16") (pintype "passive"))
    )
    (net (code "164") (name "Net-(U7-B6)") (class "Default")
      (node (ref "R106") (pin "2") (pintype "passive"))
      (node (ref "U7") (pin "15") (pinfunction "B6_15") (pintype "passive"))
    )
    (net (code "165") (name "Net-(U7-B7)") (class "Default")
      (node (ref "R107") (pin "2") (pintype "passive"))
      (node (ref "U7") (pin "14") (pinfunction "B7_14") (pintype "passive"))
    )
    (net (code "166") (name "Net-(U8-B0)") (class "Default")
      (node (ref "R108") (pin "2") (pintype "passive"))
      (node (ref "U8") (pin "21") (pinfunction "B0_21") (pintype "passive"))
    )
    (net (code "167") (name "Net-(U8-B1)") (class "Default")
      (node (ref "R109") (pin "2") (pintype "passive"))
      (node (ref "U8") (pin "20") (pinfunction "B1_20") (pintype "passive"))
    )
    (net (code "168") (name "Net-(U8-B2)") (class "Default")
      (node (ref "R110") (pin "2") (pintype "passive"))
      (node (ref "U8") (pin "19") (pinfunction "B2_19") (pintype "passive"))
    )
    (net (code "169") (name "Net-(U8-B3)") (class "Default")
      (node (ref "R111") (pin "2") (pintype "passive"))
      (node (ref "U8") (pin "18") (pinfunction "B3_18") (pintype "passive"))
    )
    (net (code "170") (name "Net-(U8-B4)") (class "Default")
      (node (ref "R112") (pin "2") (pintype "passive"))
      (node (ref "U8") (pin "17") (pinfunction "B4_17") (pintype "passive"))
    )
    (net (code "171") (name "Net-(U8-B5)") (class "Default")
      (node (ref "R113") (pin "2") (pintype "passive"))
      (node (ref "U8") (pin "16") (pinfunction "B5_16") (pintype "passive"))
    )
    (net (code "172") (name "Net-(U8-B6)") (class "Default")
      (node (ref "R114") (pin "2") (pintype "passive"))
      (node (ref "U8") (pin "15") (pinfunction "B6_15") (pintype "passive"))
    )
    (net (code "173") (name "Net-(U8-B7)") (class "Default")
      (node (ref "R115") (pin "2") (pintype "passive"))
      (node (ref "U8") (pin "14") (pinfunction "B7_14") (pintype "passive"))
    )
    (net (code "174") (name "Net-(U9-B0)") (class "Default")
      (node (ref "R116") (pin "2") (pintype "passive"))
      (node (ref "U9") (pin "21") (pinfunction "B0_21") (pintype "passive"))
    )
    (net (code "175") (name "Net-(U9-B1)") (class "Default")
      (node (ref "R117") (pin "2") (pintype "passive"))
      (node (ref "U9") (pin "20") (pinfunction "B1_20") (pintype "passive"))
    )
    (net (code "176") (name "Net-(U9-B2)") (class "Default")
      (node (ref "R118") (pin "2") (pintype "passive"))
      (node (ref "U9") (pin "19") (pinfunction "B2_19") (pintype "passive"))
    )
    (net (code "177") (name "Net-(U9-B3)") (class "Default")
      (node (ref "R119") (pin "2") (pintype "passive"))
      (node (ref "U9") (pin "18") (pinfunction "B3_18") (pintype "passive"))
    )
    (net (code "178") (name "Net-(U9-B4)") (class "Default")
      (node (ref "R120") (pin "2") (pintype "passive"))
      (node (ref "U9") (pin "17") (pinfunction "B4_17") (pintype "passive"))
    )
    (net (code "179") (name "Net-(U9-B5)") (class "Default")
      (node (ref "R121") (pin "2") (pintype "passive"))
      (node (ref "U9") (pin "16") (pinfunction "B5_16") (pintype "passive"))
    )
    (net (code "180") (name "Net-(U9-B6)") (class "Default")
      (node (ref "R122") (pin "2") (pintype "passive"))
      (node (ref "U9") (pin "15") (pinfunction "B6_15") (pintype "passive"))
    )
    (net (code "181") (name "Net-(U9-B7)") (class "Default")
      (node (ref "R123") (pin "2") (pintype "passive"))
      (node (ref "U9") (pin "14") (pinfunction "B7_14") (pintype "passive"))
    )
    (net (code "182") (name "unconnected-(U1-PadA56)") (class "Default")
      (node (ref "U1") (pin "A56") (pintype "passive"))
    )
  )
)
